# FTDI.net
KiCad netlist of a schematic drawn in Altium Designer
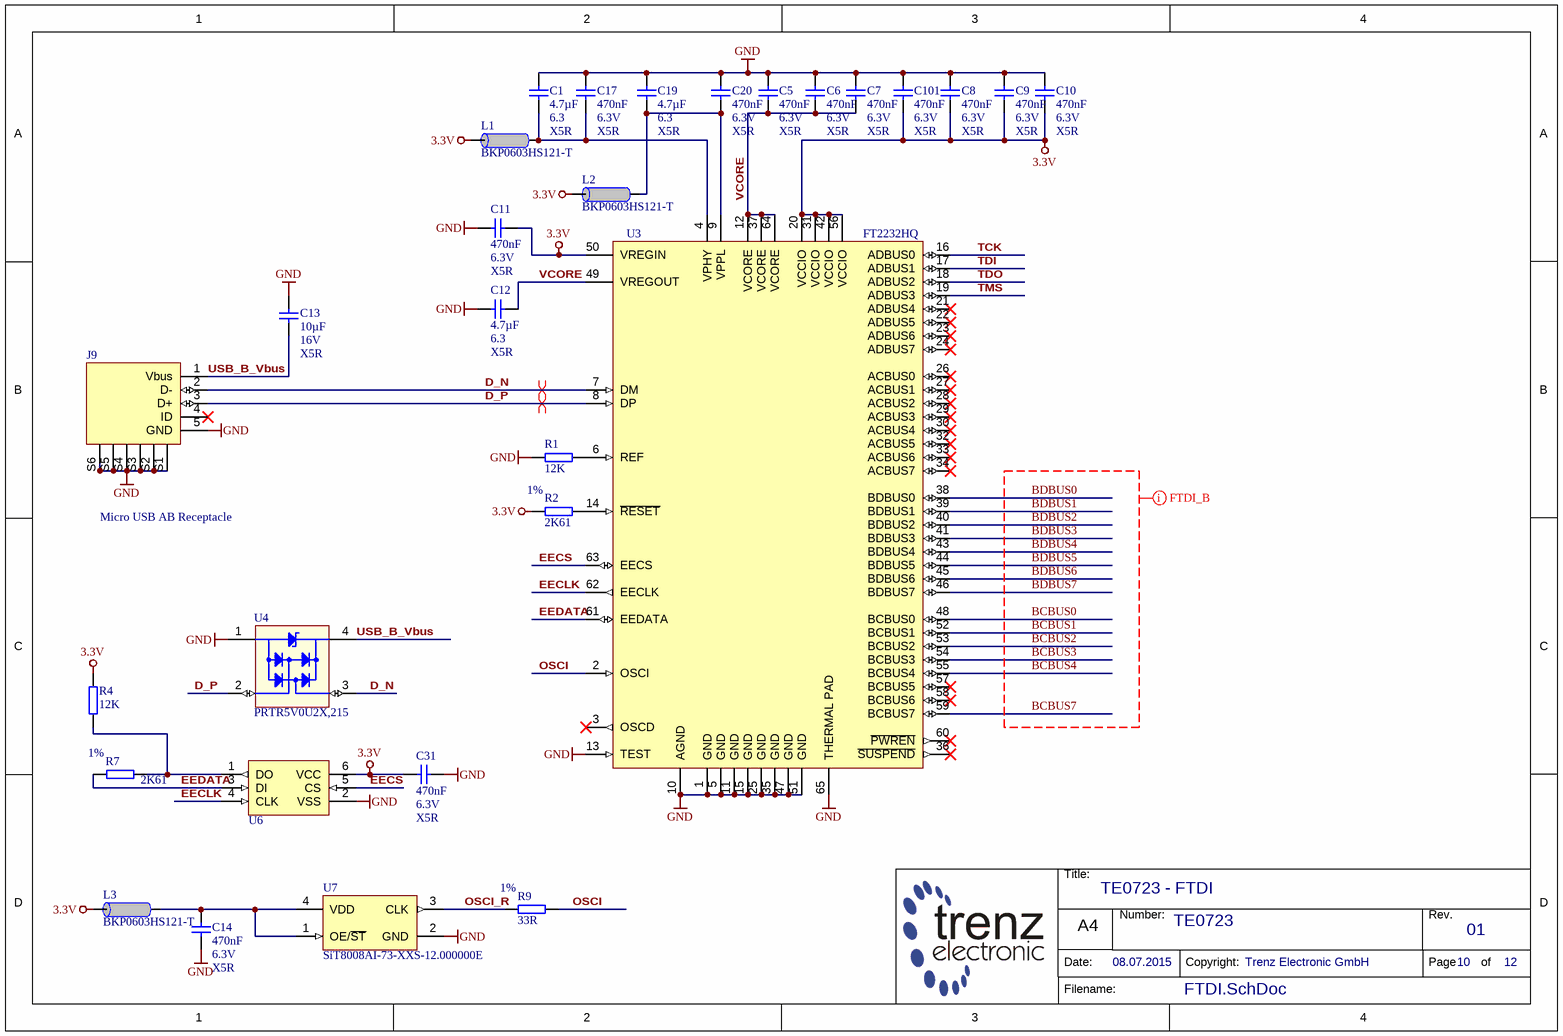
[diagram p0: FTDI.SchDoc]

(export (version "E")
  (design (tool "Eeschema 10.0.6"))
  (components
    (comp (ref "C1")
      (value "4.7µF")
      (footprint "CAPC1005X60N")
      (description "KON 4.7µF 6.3V X5R SMD 20%")
      (fields
        (field (name "VOLTAGE") "6.3")
        (field (name "TECHNOLOGY") "X5R")
        (field (name "TOLERANCE") "20%")
      )
      (libsource (lib "TE") (part "CAP-NP"))
    )
    (comp (ref "C5")
      (value "470nF")
      (footprint "CAPC0603X33N")
      (description "KON 470nF X5R 6.3V SMD 20%")
      (fields
        (field (name "VOLTAGE") "6.3V")
        (field (name "TECHNOLOGY") "X5R")
        (field (name "TOLERANCE") "20%")
      )
      (libsource (lib "TE") (part "CAP-NP"))
    )
    (comp (ref "C6")
      (value "470nF")
      (footprint "CAPC0603X33N")
      (description "KON 470nF X5R 6.3V SMD 20%")
      (fields
        (field (name "VOLTAGE") "6.3V")
        (field (name "TECHNOLOGY") "X5R")
        (field (name "TOLERANCE") "20%")
      )
      (libsource (lib "TE") (part "CAP-NP"))
    )
    (comp (ref "C7")
      (value "470nF")
      (footprint "CAPC0603X33N")
      (description "KON 470nF X5R 6.3V SMD 20%")
      (fields
        (field (name "VOLTAGE") "6.3V")
        (field (name "TECHNOLOGY") "X5R")
        (field (name "TOLERANCE") "20%")
      )
      (libsource (lib "TE") (part "CAP-NP"))
    )
    (comp (ref "C8")
      (value "470nF")
      (footprint "CAPC0603X33N")
      (description "KON 470nF X5R 6.3V SMD 20%")
      (fields
        (field (name "VOLTAGE") "6.3V")
        (field (name "TECHNOLOGY") "X5R")
        (field (name "TOLERANCE") "20%")
      )
      (libsource (lib "TE") (part "CAP-NP"))
    )
    (comp (ref "C9")
      (value "470nF")
      (footprint "CAPC0603X33N")
      (description "KON 470nF X5R 6.3V SMD 20%")
      (fields
        (field (name "VOLTAGE") "6.3V")
        (field (name "TECHNOLOGY") "X5R")
        (field (name "TOLERANCE") "20%")
      )
      (libsource (lib "TE") (part "CAP-NP"))
    )
    (comp (ref "C10")
      (value "470nF")
      (footprint "CAPC0603X33N")
      (description "KON 470nF X5R 6.3V SMD 20%")
      (fields
        (field (name "VOLTAGE") "6.3V")
        (field (name "TECHNOLOGY") "X5R")
        (field (name "TOLERANCE") "20%")
      )
      (libsource (lib "TE") (part "CAP-NP"))
    )
    (comp (ref "C11")
      (value "470nF")
      (footprint "CAPC0603X33N")
      (description "KON 470nF X5R 6.3V SMD 20%")
      (fields
        (field (name "VOLTAGE") "6.3V")
        (field (name "TECHNOLOGY") "X5R")
        (field (name "TOLERANCE") "20%")
      )
      (libsource (lib "TE") (part "CAP-NP"))
    )
    (comp (ref "C12")
      (value "4.7µF")
      (footprint "CAPC1005X60N")
      (description "KON 4.7µF 6.3V X5R SMD 20%")
      (fields
        (field (name "VOLTAGE") "6.3")
        (field (name "TECHNOLOGY") "X5R")
        (field (name "TOLERANCE") "20%")
      )
      (libsource (lib "TE") (part "CAP-NP"))
    )
    (comp (ref "C13")
      (value "10µF")
      (footprint "CAPC1608X90N")
      (description "KON 10µF 16V X5R SMD 20%")
      (fields
        (field (name "VOLTAGE") "16V")
        (field (name "TECHNOLOGY") "X5R")
        (field (name "TOLERANCE") "20%")
      )
      (libsource (lib "TE") (part "CAP-NP"))
    )
    (comp (ref "C14")
      (value "470nF")
      (footprint "CAPC0603X33N")
      (description "KON 470nF X5R 6.3V SMD 20%")
      (fields
        (field (name "VOLTAGE") "6.3V")
        (field (name "TECHNOLOGY") "X5R")
        (field (name "TOLERANCE") "20%")
      )
      (libsource (lib "TE") (part "CAP-NP"))
    )
    (comp (ref "C17")
      (value "470nF")
      (footprint "CAPC0603X33N")
      (description "KON 470nF X5R 6.3V SMD 20%")
      (fields
        (field (name "VOLTAGE") "6.3V")
        (field (name "TECHNOLOGY") "X5R")
        (field (name "TOLERANCE") "20%")
      )
      (libsource (lib "TE") (part "CAP-NP"))
    )
    (comp (ref "C19")
      (value "4.7µF")
      (footprint "CAPC1005X60N")
      (description "KON 4.7µF 6.3V X5R SMD 20%")
      (fields
        (field (name "VOLTAGE") "6.3")
        (field (name "TECHNOLOGY") "X5R")
        (field (name "TOLERANCE") "20%")
      )
      (libsource (lib "TE") (part "CAP-NP"))
    )
    (comp (ref "C20")
      (value "470nF")
      (footprint "CAPC0603X33N")
      (description "KON 470nF X5R 6.3V SMD 20%")
      (fields
        (field (name "VOLTAGE") "6.3V")
        (field (name "TECHNOLOGY") "X5R")
        (field (name "TOLERANCE") "20%")
      )
      (libsource (lib "TE") (part "CAP-NP"))
    )
    (comp (ref "C31")
      (value "470nF")
      (footprint "CAPC0603X33N")
      (description "KON 470nF X5R 6.3V SMD 20%")
      (fields
        (field (name "VOLTAGE") "6.3V")
        (field (name "TECHNOLOGY") "X5R")
        (field (name "TOLERANCE") "20%")
      )
      (libsource (lib "TE") (part "CAP-NP"))
    )
    (comp (ref "C101")
      (value "470nF")
      (footprint "CAPC0603X33N")
      (description "KON 470nF X5R 6.3V SMD 20%")
      (fields
        (field (name "VOLTAGE") "6.3V")
        (field (name "TECHNOLOGY") "X5R")
        (field (name "TOLERANCE") "20%")
      )
      (libsource (lib "TE") (part "CAP-NP"))
    )
    (comp (ref "J9")
      (value "Micro USB AB Receptacle")
      (footprint "Micro USB ZX62-xx-5PA")
      (description "Micro USB AB Buchse")
      (libsource (lib "TE") (part "M USB SMD"))
    )
    (comp (ref "L1")
      (value "BKP0603HS121-T")
      (footprint "INDC0603X33N")
      (description "Ferritdurchführung SMD 0201")
      (fields (field (name "TOLERANCE") "25%"))
      (libsource (lib "TE") (part "Ferritperle"))
    )
    (comp (ref "L2")
      (value "BKP0603HS121-T")
      (footprint "INDC0603X33N")
      (description "Ferritdurchführung SMD 0201")
      (fields (field (name "TOLERANCE") "25%"))
      (libsource (lib "TE") (part "Ferritperle"))
    )
    (comp (ref "L3")
      (value "BKP0603HS121-T")
      (footprint "INDC0603X33N")
      (description "Ferritdurchführung SMD 0201")
      (fields (field (name "TOLERANCE") "25%"))
      (libsource (lib "TE") (part "Ferritperle"))
    )
    (comp (ref "R1")
      (value "12K")
      (footprint "RESC1005X40N")
      (description "WID SMD 12K 1% 0,063W")
      (libsource (lib "TE") (part "RES"))
    )
    (comp (ref "R2")
      (value "2K61")
      (footprint "RESC1005X40N")
      (description "WID SMD 2K61 1% 0,063W")
      (fields (field (name "TOLERANCE") "1%"))
      (libsource (lib "TE") (part "RES"))
    )
    (comp (ref "R4")
      (value "12K")
      (footprint "RESC1005X40N")
      (description "WID SMD 12K 1% 0,063W")
      (libsource (lib "TE") (part "RES"))
    )
    (comp (ref "R7")
      (value "2K61")
      (footprint "RESC1005X40N")
      (description "WID SMD 2K61 1% 0,063W")
      (fields (field (name "TOLERANCE") "1%"))
      (libsource (lib "TE") (part "RES"))
    )
    (comp (ref "R9")
      (value "33R")
      (footprint "RESC0603X26N")
      (description "WID SMD 33R 1% 0,05W")
      (fields (field (name "TOLERANCE") "1%"))
      (libsource (lib "TE") (part "RES"))
    )
    (comp (ref "U3")
      (value "FT2232HQ")
      (footprint "QFN50P900X900X100-65N-445")
      (libsource (lib "TE") (part "FT2232H"))
    )
    (comp (ref "U4")
      (value "PRTR5V0U2X,215")
      (footprint "SOT190P229X114-4N")
      (libsource (lib "TE") (part "CD143A-SRxx"))
    )
    (comp (ref "U6")
      (value "93AA56BT-I/OT")
      (footprint "SOT95P280X145-6N")
      (libsource (lib "TE") (part "93AA56x-OT"))
    )
    (comp (ref "U7")
      (value "SiT8008AI-73-XXS-12.000000E")
      (footprint "2016")
      (description "SiT8008AI-73-XXS-12.000000E MEMS Oszillator 12MHz")
      (libsource (lib "TE") (part "SiT8103"))
    )
  )
  (nets
    (net (code "1") (name "/BCBUS0") (class "Default")
      (node (ref "U3") (pin "48") (pinfunction "BCBUS0_48") (pintype "bidirectional"))
    )
    (net (code "2") (name "/BCBUS1") (class "Default")
      (node (ref "U3") (pin "52") (pinfunction "BCBUS1_52") (pintype "bidirectional"))
    )
    (net (code "3") (name "/BCBUS2") (class "Default")
      (node (ref "U3") (pin "53") (pinfunction "BCBUS2_53") (pintype "bidirectional"))
    )
    (net (code "4") (name "/BCBUS3") (class "Default")
      (node (ref "U3") (pin "54") (pinfunction "BCBUS3_54") (pintype "bidirectional"))
    )
    (net (code "5") (name "/BCBUS4") (class "Default")
      (node (ref "U3") (pin "55") (pinfunction "BCBUS4_55") (pintype "bidirectional"))
    )
    (net (code "6") (name "/BCBUS7") (class "Default")
      (node (ref "U3") (pin "59") (pinfunction "BCBUS7_59") (pintype "bidirectional"))
    )
    (net (code "7") (name "/BDBUS0") (class "Default")
      (node (ref "U3") (pin "38") (pinfunction "BDBUS0_38") (pintype "bidirectional"))
    )
    (net (code "8") (name "/BDBUS1") (class "Default")
      (node (ref "U3") (pin "39") (pinfunction "BDBUS1_39") (pintype "bidirectional"))
    )
    (net (code "9") (name "/BDBUS2") (class "Default")
      (node (ref "U3") (pin "40") (pinfunction "BDBUS2_40") (pintype "bidirectional"))
    )
    (net (code "10") (name "/BDBUS3") (class "Default")
      (node (ref "U3") (pin "41") (pinfunction "BDBUS3_41") (pintype "bidirectional"))
    )
    (net (code "11") (name "/BDBUS4") (class "Default")
      (node (ref "U3") (pin "43") (pinfunction "BDBUS4_43") (pintype "bidirectional"))
    )
    (net (code "12") (name "/BDBUS5") (class "Default")
      (node (ref "U3") (pin "44") (pinfunction "BDBUS5_44") (pintype "bidirectional"))
    )
    (net (code "13") (name "/BDBUS6") (class "Default")
      (node (ref "U3") (pin "45") (pinfunction "BDBUS6_45") (pintype "bidirectional"))
    )
    (net (code "14") (name "/BDBUS7") (class "Default")
      (node (ref "U3") (pin "46") (pinfunction "BDBUS7_46") (pintype "bidirectional"))
    )
    (net (code "15") (name "/D_N") (class "Default")
      (node (ref "J9") (pin "2") (pinfunction "D-_2") (pintype "bidirectional"))
      (node (ref "U3") (pin "7") (pinfunction "DM_7") (pintype "input"))
      (node (ref "U4") (pin "3") (pinfunction "I/O_3") (pintype "bidirectional"))
    )
    (net (code "16") (name "/D_P") (class "Default")
      (node (ref "J9") (pin "3") (pinfunction "D+_3") (pintype "bidirectional"))
      (node (ref "U3") (pin "8") (pinfunction "DP_8") (pintype "input"))
      (node (ref "U4") (pin "2") (pinfunction "I/O_2") (pintype "bidirectional"))
    )
    (net (code "17") (name "/EECLK") (class "Default")
      (node (ref "U3") (pin "62") (pinfunction "EECLK_62") (pintype "output"))
      (node (ref "U6") (pin "4") (pinfunction "CLK_4") (pintype "input"))
    )
    (net (code "18") (name "/EECS") (class "Default")
      (node (ref "U3") (pin "63") (pinfunction "EECS_63") (pintype "bidirectional"))
      (node (ref "U6") (pin "5") (pinfunction "CS_5") (pintype "input"))
    )
    (net (code "19") (name "/EEDATA") (class "Default")
      (node (ref "R7") (pin "1") (pinfunction "1_1") (pintype "passive"))
      (node (ref "U3") (pin "61") (pinfunction "EEDATA_61") (pintype "bidirectional"))
      (node (ref "U6") (pin "3") (pinfunction "DI_3") (pintype "input"))
    )
    (net (code "20") (name "/OSCI") (class "Default")
      (node (ref "R9") (pin "2") (pinfunction "2_2") (pintype "passive"))
      (node (ref "U3") (pin "2") (pinfunction "OSCI_2") (pintype "input"))
    )
    (net (code "21") (name "/OSCI_R") (class "Default")
      (node (ref "R9") (pin "1") (pinfunction "1_1") (pintype "passive"))
      (node (ref "U7") (pin "3") (pinfunction "CLK_3") (pintype "output"))
    )
    (net (code "22") (name "/TCK") (class "Default")
      (node (ref "U3") (pin "16") (pinfunction "ADBUS0_16") (pintype "bidirectional"))
    )
    (net (code "23") (name "/TDI") (class "Default")
      (node (ref "U3") (pin "17") (pinfunction "ADBUS1_17") (pintype "bidirectional"))
    )
    (net (code "24") (name "/TDO") (class "Default")
      (node (ref "U3") (pin "18") (pinfunction "ADBUS2_18") (pintype "bidirectional"))
    )
    (net (code "25") (name "/TMS") (class "Default")
      (node (ref "U3") (pin "19") (pinfunction "ADBUS3_19") (pintype "bidirectional"))
    )
    (net (code "26") (name "/USB_B_Vbus") (class "Default")
      (node (ref "C13") (pin "2") (pinfunction "2_2") (pintype "passive"))
      (node (ref "J9") (pin "1") (pinfunction "Vbus_1") (pintype "power_in"))
      (node (ref "U4") (pin "4") (pinfunction "REF_4") (pintype "passive"))
    )
    (net (code "27") (name "/VCORE") (class "Default")
      (node (ref "C12") (pin "2") (pinfunction "2_2") (pintype "passive"))
      (node (ref "C5") (pin "1") (pinfunction "1_1") (pintype "passive"))
      (node (ref "C6") (pin "1") (pinfunction "1_1") (pintype "passive"))
      (node (ref "C7") (pin "1") (pinfunction "1_1") (pintype "passive"))
      (node (ref "U3") (pin "12") (pinfunction "VCORE_12") (pintype "power_in"))
      (node (ref "U3") (pin "37") (pinfunction "VCORE_37") (pintype "power_in"))
      (node (ref "U3") (pin "49") (pinfunction "VREGOUT_49") (pintype "power_in"))
      (node (ref "U3") (pin "64") (pinfunction "VCORE_64") (pintype "power_in"))
    )
    (net (code "28") (name "3.3V") (class "Default")
      (node (ref "C10") (pin "1") (pinfunction "1_1") (pintype "passive"))
      (node (ref "C101") (pin "1") (pinfunction "1_1") (pintype "passive"))
      (node (ref "C11") (pin "2") (pinfunction "2_2") (pintype "passive"))
      (node (ref "C31") (pin "1") (pinfunction "1_1") (pintype "passive"))
      (node (ref "C8") (pin "1") (pinfunction "1_1") (pintype "passive"))
      (node (ref "C9") (pin "1") (pinfunction "1_1") (pintype "passive"))
      (node (ref "L1") (pin "2") (pinfunction "2_2") (pintype "passive"))
      (node (ref "L2") (pin "2") (pinfunction "2_2") (pintype "passive"))
      (node (ref "L3") (pin "2") (pinfunction "2_2") (pintype "passive"))
      (node (ref "R2") (pin "1") (pinfunction "1_1") (pintype "passive"))
      (node (ref "R4") (pin "2") (pinfunction "2_2") (pintype "passive"))
      (node (ref "U3") (pin "20") (pinfunction "VCCIO_20") (pintype "power_in"))
      (node (ref "U3") (pin "31") (pinfunction "VCCIO_31") (pintype "power_in"))
      (node (ref "U3") (pin "42") (pinfunction "VCCIO_42") (pintype "power_in"))
      (node (ref "U3") (pin "50") (pinfunction "VREGIN_50") (pintype "power_in"))
      (node (ref "U3") (pin "56") (pinfunction "VCCIO_56") (pintype "power_in"))
      (node (ref "U6") (pin "6") (pinfunction "VCC_6") (pintype "power_in"))
    )
    (net (code "29") (name "GND") (class "Default")
      (node (ref "C1") (pin "2") (pinfunction "2_2") (pintype "passive"))
      (node (ref "C10") (pin "2") (pinfunction "2_2") (pintype "passive"))
      (node (ref "C101") (pin "2") (pinfunction "2_2") (pintype "passive"))
      (node (ref "C11") (pin "1") (pinfunction "1_1") (pintype "passive"))
      (node (ref "C12") (pin "1") (pinfunction "1_1") (pintype "passive"))
      (node (ref "C13") (pin "1") (pinfunction "1_1") (pintype "passive"))
      (node (ref "C14") (pin "1") (pinfunction "1_1") (pintype "passive"))
      (node (ref "C17") (pin "2") (pinfunction "2_2") (pintype "passive"))
      (node (ref "C19") (pin "2") (pinfunction "2_2") (pintype "passive"))
      (node (ref "C20") (pin "2") (pinfunction "2_2") (pintype "passive"))
      (node (ref "C31") (pin "2") (pinfunction "2_2") (pintype "passive"))
      (node (ref "C5") (pin "2") (pinfunction "2_2") (pintype "passive"))
      (node (ref "C6") (pin "2") (pinfunction "2_2") (pintype "passive"))
      (node (ref "C7") (pin "2") (pinfunction "2_2") (pintype "passive"))
      (node (ref "C8") (pin "2") (pinfunction "2_2") (pintype "passive"))
      (node (ref "C9") (pin "2") (pinfunction "2_2") (pintype "passive"))
      (node (ref "J9") (pin "5") (pinfunction "GND_5") (pintype "power_in"))
      (node (ref "J9") (pin "S1") (pinfunction "S1_S1") (pintype "passive"))
      (node (ref "J9") (pin "S2") (pinfunction "S2_S2") (pintype "passive"))
      (node (ref "J9") (pin "S3") (pinfunction "S3_S3") (pintype "passive"))
      (node (ref "J9") (pin "S4") (pinfunction "S4_S4") (pintype "passive"))
      (node (ref "J9") (pin "S5") (pinfunction "S5_S5") (pintype "passive"))
      (node (ref "J9") (pin "S6") (pinfunction "S6_S6") (pintype "passive"))
      (node (ref "R1") (pin "1") (pinfunction "1_1") (pintype "passive"))
      (node (ref "U3") (pin "1") (pinfunction "GND_1") (pintype "power_in"))
      (node (ref "U3") (pin "10") (pinfunction "AGND_10") (pintype "power_in"))
      (node (ref "U3") (pin "11") (pinfunction "GND_11") (pintype "power_in"))
      (node (ref "U3") (pin "13") (pinfunction "TEST_13") (pintype "input"))
      (node (ref "U3") (pin "15") (pinfunction "GND_15") (pintype "power_in"))
      (node (ref "U3") (pin "25") (pinfunction "GND_25") (pintype "power_in"))
      (node (ref "U3") (pin "35") (pinfunction "GND_35") (pintype "power_in"))
      (node (ref "U3") (pin "47") (pinfunction "GND_47") (pintype "power_in"))
      (node (ref "U3") (pin "5") (pinfunction "GND_5") (pintype "power_in"))
      (node (ref "U3") (pin "51") (pinfunction "GND_51") (pintype "power_in"))
      (node (ref "U3") (pin "65") (pinfunction "THERMAL_PAD_65") (pintype "passive"))
      (node (ref "U4") (pin "1") (pinfunction "GND_1") (pintype "passive"))
      (node (ref "U6") (pin "2") (pinfunction "VSS_2") (pintype "power_in"))
      (node (ref "U7") (pin "2") (pinfunction "GND_2") (pintype "power_in"))
    )
    (net (code "30") (name "Net-(U3-REF)") (class "Default")
      (node (ref "R1") (pin "2") (pinfunction "2_2") (pintype "passive"))
      (node (ref "U3") (pin "6") (pinfunction "REF_6") (pintype "input"))
    )
    (net (code "31") (name "Net-(U3-VPHY)") (class "Default")
      (node (ref "C1") (pin "1") (pinfunction "1_1") (pintype "passive"))
      (node (ref "C17") (pin "1") (pinfunction "1_1") (pintype "passive"))
      (node (ref "L1") (pin "1") (pinfunction "1_1") (pintype "passive"))
      (node (ref "U3") (pin "4") (pinfunction "VPHY_4") (pintype "power_in"))
    )
    (net (code "32") (name "Net-(U3-VPPL)") (class "Default")
      (node (ref "C19") (pin "1") (pinfunction "1_1") (pintype "passive"))
      (node (ref "C20") (pin "1") (pinfunction "1_1") (pintype "passive"))
      (node (ref "L2") (pin "1") (pinfunction "1_1") (pintype "passive"))
      (node (ref "U3") (pin "9") (pinfunction "VPPL_9") (pintype "power_in"))
    )
    (net (code "33") (name "Net-(U3-~{RESET})") (class "Default")
      (node (ref "R2") (pin "2") (pinfunction "2_2") (pintype "passive"))
      (node (ref "U3") (pin "14") (pinfunction "~{RESET}_14") (pintype "input"))
    )
    (net (code "34") (name "Net-(U6-DO)") (class "Default")
      (node (ref "R4") (pin "1") (pinfunction "1_1") (pintype "passive"))
      (node (ref "R7") (pin "2") (pinfunction "2_2") (pintype "passive"))
      (node (ref "U6") (pin "1") (pinfunction "DO_1") (pintype "output"))
    )
    (net (code "35") (name "Net-(U7-OE{slash}~{ST})") (class "Default")
      (node (ref "C14") (pin "2") (pinfunction "2_2") (pintype "passive"))
      (node (ref "L3") (pin "1") (pinfunction "1_1") (pintype "passive"))
      (node (ref "U7") (pin "1") (pinfunction "OE/~{ST}_1") (pintype "input"))
      (node (ref "U7") (pin "4") (pinfunction "VDD_4") (pintype "power_in"))
    )
    (net (code "36") (name "unconnected-(J9-ID-Pad4)") (class "Default")
      (node (ref "J9") (pin "4") (pinfunction "ID_4") (pintype "passive+no_connect"))
    )
    (net (code "37") (name "unconnected-(U3-ACBUS0-Pad26)") (class "Default")
      (node (ref "U3") (pin "26") (pinfunction "ACBUS0_26") (pintype "bidirectional+no_connect"))
    )
    (net (code "38") (name "unconnected-(U3-ACBUS1-Pad27)") (class "Default")
      (node (ref "U3") (pin "27") (pinfunction "ACBUS1_27") (pintype "bidirectional+no_connect"))
    )
    (net (code "39") (name "unconnected-(U3-ACBUS2-Pad28)") (class "Default")
      (node (ref "U3") (pin "28") (pinfunction "ACBUS2_28") (pintype "bidirectional+no_connect"))
    )
    (net (code "40") (name "unconnected-(U3-ACBUS3-Pad29)") (class "Default")
      (node (ref "U3") (pin "29") (pinfunction "ACBUS3_29") (pintype "bidirectional+no_connect"))
    )
    (net (code "41") (name "unconnected-(U3-ACBUS4-Pad30)") (class "Default")
      (node (ref "U3") (pin "30") (pinfunction "ACBUS4_30") (pintype "bidirectional+no_connect"))
    )
    (net (code "42") (name "unconnected-(U3-ACBUS5-Pad32)") (class "Default")
      (node (ref "U3") (pin "32") (pinfunction "ACBUS5_32") (pintype "bidirectional+no_connect"))
    )
    (net (code "43") (name "unconnected-(U3-ACBUS6-Pad33)") (class "Default")
      (node (ref "U3") (pin "33") (pinfunction "ACBUS6_33") (pintype "bidirectional+no_connect"))
    )
    (net (code "44") (name "unconnected-(U3-ACBUS7-Pad34)") (class "Default")
      (node (ref "U3") (pin "34") (pinfunction "ACBUS7_34") (pintype "bidirectional+no_connect"))
    )
    (net (code "45") (name "unconnected-(U3-ADBUS4-Pad21)") (class "Default")
      (node (ref "U3") (pin "21") (pinfunction "ADBUS4_21") (pintype "bidirectional+no_connect"))
    )
    (net (code "46") (name "unconnected-(U3-ADBUS5-Pad22)") (class "Default")
      (node (ref "U3") (pin "22") (pinfunction "ADBUS5_22") (pintype "bidirectional+no_connect"))
    )
    (net (code "47") (name "unconnected-(U3-ADBUS6-Pad23)") (class "Default")
      (node (ref "U3") (pin "23") (pinfunction "ADBUS6_23") (pintype "bidirectional+no_connect"))
    )
    (net (code "48") (name "unconnected-(U3-ADBUS7-Pad24)") (class "Default")
      (node (ref "U3") (pin "24") (pinfunction "ADBUS7_24") (pintype "bidirectional+no_connect"))
    )
    (net (code "49") (name "unconnected-(U3-BCBUS5-Pad57)") (class "Default")
      (node (ref "U3") (pin "57") (pinfunction "BCBUS5_57") (pintype "bidirectional+no_connect"))
    )
    (net (code "50") (name "unconnected-(U3-BCBUS6-Pad58)") (class "Default")
      (node (ref "U3") (pin "58") (pinfunction "BCBUS6_58") (pintype "bidirectional+no_connect"))
    )
    (net (code "51") (name "unconnected-(U3-OSCD-Pad3)") (class "Default")
      (node (ref "U3") (pin "3") (pinfunction "OSCD_3") (pintype "output+no_connect"))
    )
    (net (code "52") (name "unconnected-(U3-~{PWREN}-Pad60)") (class "Default")
      (node (ref "U3") (pin "60") (pinfunction "~{PWREN}_60") (pintype "output+no_connect"))
    )
    (net (code "53") (name "unconnected-(U3-~{SUSPEND}-Pad36)") (class "Default")
      (node (ref "U3") (pin "36") (pinfunction "~{SUSPEND}_36") (pintype "output+no_connect"))
    )
  )
)
